# Power_Supply.net
KiCad netlist of a schematic drawn in EAGLE
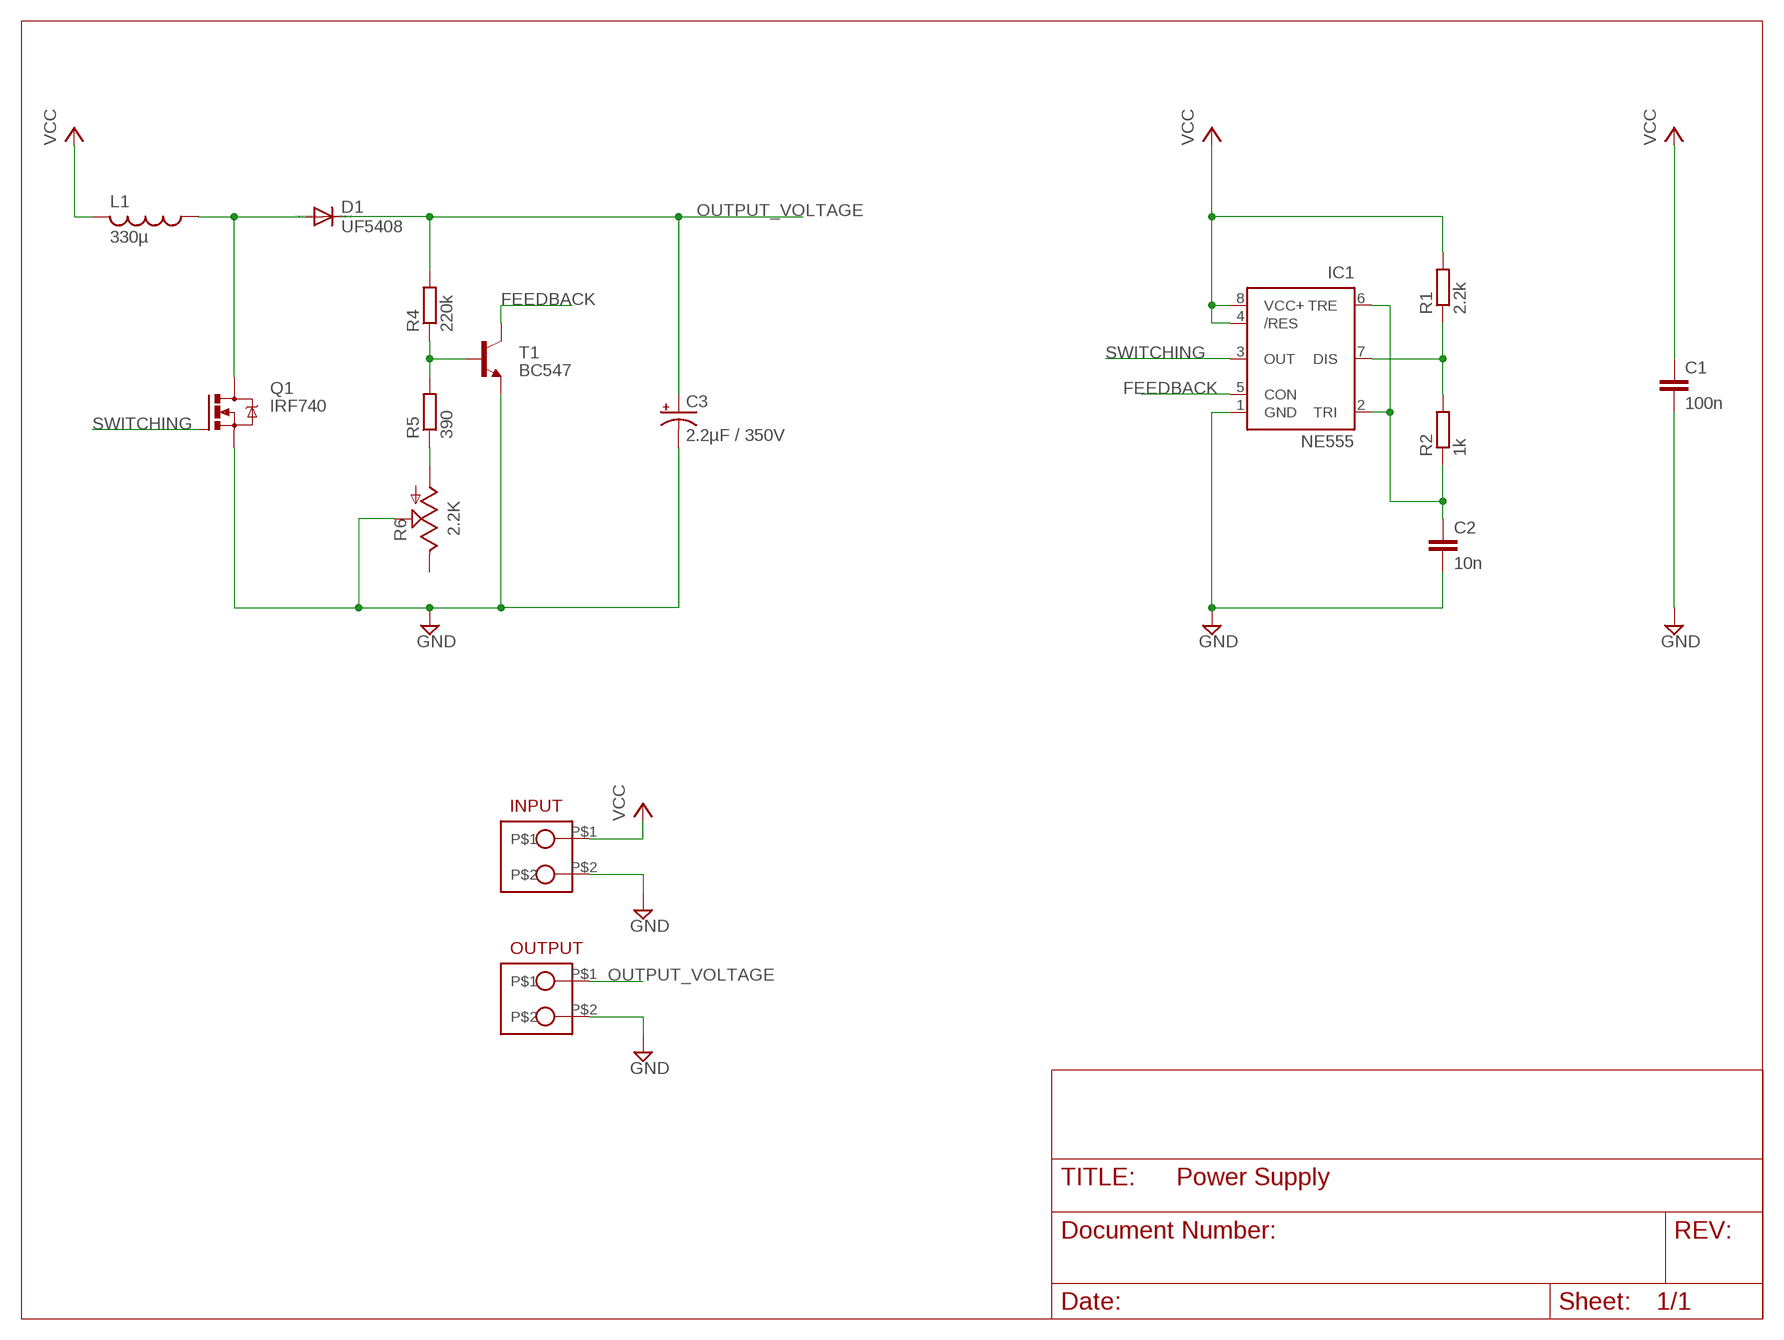
[diagram p0: schematic, sheet 1]

(export (version "E")
  (design (tool "Eeschema 10.0.6"))
  (components
    (comp (ref "C1")
      (value "100n")
      (footprint "eagle-import:C050-030X075")
      (libsource (lib "eagle-import") (part "C-EU050-030X075"))
    )
    (comp (ref "C2")
      (value "10n")
      (footprint "eagle-import:C050-030X075")
      (libsource (lib "eagle-import") (part "C-EU050-030X075"))
    )
    (comp (ref "C3")
      (value "2.2µF / 350V")
      (footprint "eagle-import:TAP5-80")
      (libsource (lib "eagle-import") (part "CPOL-USTAP5-80"))
    )
    (comp (ref "D1")
      (value "UF5408")
      (footprint "eagle-import:DO201-15")
      (libsource (lib "eagle-import") (part "UF5400"))
    )
    (comp (ref "IC1")
      (value "NE555")
      (footprint "eagle-import:DIL-08")
      (fields (field (name "MF") "Arrow Electronics") (field (name "MPN") "NE555N"))
      (libsource (lib "eagle-import") (part "NE555"))
    )
    (comp (ref "INPUT")
      (value "CON_2_SIL")
      (footprint "eagle-import:SIL_2_0.2INCH")
      (libsource (lib "eagle-import") (part "CON_2_SIL"))
    )
    (comp (ref "L1")
      (value "330µ")
      (footprint "eagle-import:6000-XXXX-RC")
      (libsource (lib "eagle-import") (part "L-US6000-XXX-RC"))
    )
    (comp (ref "OUTPUT")
      (value "CON_2_SIL")
      (footprint "eagle-import:SIL_2_0.2INCH")
      (libsource (lib "eagle-import") (part "CON_2_SIL"))
    )
    (comp (ref "Q1")
      (value "IRF740")
      (footprint "eagle-import:TO220BV")
      (libsource (lib "eagle-import") (part "IRF740"))
    )
    (comp (ref "R1")
      (value "2.2k")
      (footprint "eagle-import:0207_10")
      (libsource (lib "eagle-import") (part "R-EU_0207/10"))
    )
    (comp (ref "R2")
      (value "1k")
      (footprint "eagle-import:0207_10")
      (libsource (lib "eagle-import") (part "R-EU_0207/10"))
    )
    (comp (ref "R4")
      (value "220k")
      (footprint "eagle-import:0207_10")
      (libsource (lib "eagle-import") (part "R-EU_0207/10"))
    )
    (comp (ref "R5")
      (value "390")
      (footprint "eagle-import:0207_10")
      (libsource (lib "eagle-import") (part "R-EU_0207/10"))
    )
    (comp (ref "R6")
      (value "2.2K")
      (footprint "eagle-import:CA9V")
      (libsource (lib "eagle-import") (part "TRIM_US-CA9V"))
    )
    (comp (ref "T1")
      (value "BC547")
      (footprint "eagle-import:TO92")
      (libsource (lib "eagle-import") (part "BC547"))
    )
  )
  (nets
    (net (code "1") (name "/FEEDBACK") (class "Default")
      (node (ref "IC1") (pin "5") (pinfunction "CON_5") (pintype "input"))
      (node (ref "T1") (pin "3") (pinfunction "C_3") (pintype "passive"))
    )
    (net (code "2") (name "/OUTPUT_VOLTAGE") (class "Default")
      (node (ref "C3") (pin "+") (pinfunction "+_+") (pintype "passive"))
      (node (ref "D1") (pin "C") (pinfunction "C_C") (pintype "passive"))
      (node (ref "OUTPUT") (pin "P$1") (pinfunction "P$1_P$1") (pintype "bidirectional"))
      (node (ref "R4") (pin "2") (pinfunction "2_2") (pintype "passive"))
    )
    (net (code "3") (name "/SWITCHING") (class "Default")
      (node (ref "IC1") (pin "3") (pinfunction "OUT_3") (pintype "output"))
      (node (ref "Q1") (pin "G") (pinfunction "G_G") (pintype "passive"))
    )
    (net (code "4") (name "GND") (class "Default")
      (node (ref "C1") (pin "2") (pinfunction "2_2") (pintype "passive"))
      (node (ref "C2") (pin "2") (pinfunction "2_2") (pintype "passive"))
      (node (ref "C3") (pin "-") (pinfunction "-_-") (pintype "passive"))
      (node (ref "IC1") (pin "1") (pinfunction "GND_1") (pintype "power_in"))
      (node (ref "INPUT") (pin "P$2") (pinfunction "P$2_P$2") (pintype "bidirectional"))
      (node (ref "OUTPUT") (pin "P$2") (pinfunction "P$2_P$2") (pintype "bidirectional"))
      (node (ref "Q1") (pin "S") (pinfunction "S_S") (pintype "passive"))
      (node (ref "R6") (pin "S") (pinfunction "S_S") (pintype "passive"))
      (node (ref "T1") (pin "1") (pinfunction "E_1") (pintype "passive"))
    )
    (net (code "5") (name "Net-(D1-PadA)") (class "Default")
      (node (ref "D1") (pin "A") (pinfunction "A_A") (pintype "passive"))
      (node (ref "L1") (pin "1") (pinfunction "1_1") (pintype "passive"))
      (node (ref "Q1") (pin "D") (pinfunction "D_D") (pintype "passive"))
    )
    (net (code "6") (name "Net-(IC1-DIS)") (class "Default")
      (node (ref "IC1") (pin "7") (pinfunction "DIS_7") (pintype "input"))
      (node (ref "R1") (pin "1") (pinfunction "1_1") (pintype "passive"))
      (node (ref "R2") (pin "2") (pinfunction "2_2") (pintype "passive"))
    )
    (net (code "7") (name "Net-(IC1-TRE)") (class "Default")
      (node (ref "C2") (pin "1") (pinfunction "1_1") (pintype "passive"))
      (node (ref "IC1") (pin "2") (pinfunction "TRI_2") (pintype "input"))
      (node (ref "IC1") (pin "6") (pinfunction "TRE_6") (pintype "input"))
      (node (ref "R2") (pin "1") (pinfunction "1_1") (pintype "passive"))
    )
    (net (code "8") (name "Net-(R5-Pad1)") (class "Default")
      (node (ref "R5") (pin "1") (pinfunction "1_1") (pintype "passive"))
      (node (ref "R6") (pin "A") (pinfunction "A_A") (pintype "passive"))
    )
    (net (code "9") (name "Net-(T1-B)") (class "Default")
      (node (ref "R4") (pin "1") (pinfunction "1_1") (pintype "passive"))
      (node (ref "R5") (pin "2") (pinfunction "2_2") (pintype "passive"))
      (node (ref "T1") (pin "2") (pinfunction "B_2") (pintype "passive"))
    )
    (net (code "10") (name "VCC") (class "Default")
      (node (ref "C1") (pin "1") (pinfunction "1_1") (pintype "passive"))
      (node (ref "IC1") (pin "4") (pinfunction "/RES_4") (pintype "input"))
      (node (ref "IC1") (pin "8") (pinfunction "VCC+_8") (pintype "power_in"))
      (node (ref "INPUT") (pin "P$1") (pinfunction "P$1_P$1") (pintype "bidirectional"))
      (node (ref "L1") (pin "2") (pinfunction "2_2") (pintype "passive"))
      (node (ref "R1") (pin "2") (pinfunction "2_2") (pintype "passive"))
    )
    (net (code "11") (name "unconnected-(R6-PadE)") (class "Default")
      (node (ref "R6") (pin "E") (pinfunction "E_E") (pintype "passive"))
    )
  )
)
